# HBridge_Design.net
KiCad netlist of a schematic drawn in Altium Designer
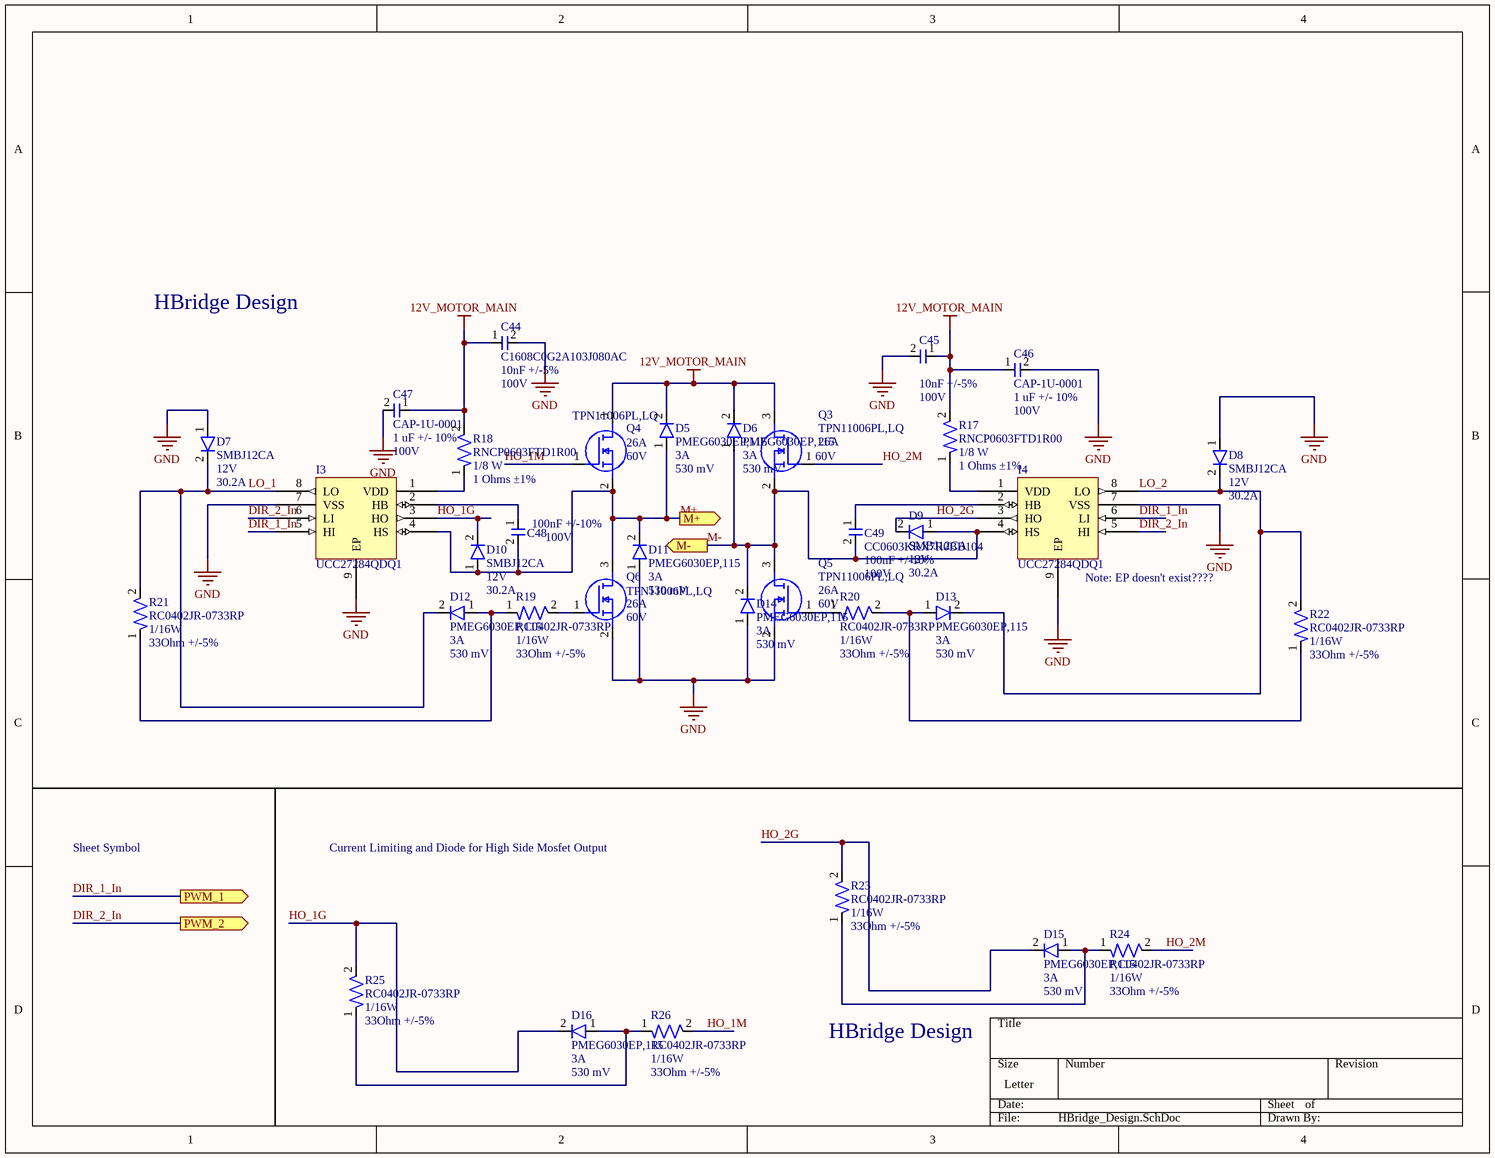
[diagram p0: HBridge_Design.SchDoc]

(export (version "E")
  (design (tool "Eeschema 10.0.6"))
  (components
    (comp (ref "C44")
      (value "C1608C0G2A103J080AC")
      (footprint "CAP-0603")
      (description "CAP CER 10000PF 100V C0G 0603")
      (fields
        (field (name "MANUFACTURER") "TDK Corporation")
        (field (name "CAPACITANCE") "10nF +/-5%")
        (field (name "VOLTAGE RATING") "100V")
      )
      (libsource (lib "MasterLib") (part "CAP-10N-0002"))
    )
    (comp (ref "C45")
      (value "C1608C0G2A103J080AC")
      (footprint "CAP-0603")
      (description "CAP CER 10000PF 100V C0G 0603")
      (fields
        (field (name "MANUFACTURER") "TDK Corporation")
        (field (name "CAPACITANCE") "10nF +/-5%")
        (field (name "VOLTAGE RATING") "100V")
      )
      (libsource (lib "MasterLib") (part "CAP-10N-0002"))
    )
    (comp (ref "C46")
      (value "CAP-1U-0001")
      (footprint "CAP-1206 - duplicate")
      (description "1 µF ±10% 100V Ceramic Capacitor X7R 1206 (3216 Metric)")
      (fields (field (name "CAPACITANCE") "1 uF +/- 10%") (field (name "VOLTAGE") "100V"))
      (libsource (lib "MasterLib") (part "CAP-1U-0001"))
    )
    (comp (ref "C47")
      (value "CAP-1U-0001")
      (footprint "CAP-1206 - duplicate")
      (description "1 µF ±10% 100V Ceramic Capacitor X7R 1206 (3216 Metric)")
      (fields (field (name "CAPACITANCE") "1 uF +/- 10%") (field (name "VOLTAGE") "100V"))
      (libsource (lib "MasterLib") (part "CAP-1U-0001"))
    )
    (comp (ref "C48")
      (value "CC0603KRX7R0BB104")
      (footprint "CAP-0603")
      (description "CAP CER 0.1UF 100V X7R 0603")
      (fields
        (field (name "MANUFACTURER") "YAGEO")
        (field (name "CAPACITANCE") "100nF +/-10%")
        (field (name "VOLTAGE RATING") "100V")
      )
      (libsource (lib "MasterLib") (part "CAP-100N-0001"))
    )
    (comp (ref "C49")
      (value "CC0603KRX7R0BB104")
      (footprint "CAP-0603")
      (description "CAP CER 0.1UF 100V X7R 0603")
      (fields
        (field (name "MANUFACTURER") "YAGEO")
        (field (name "CAPACITANCE") "100nF +/-10%")
        (field (name "VOLTAGE RATING") "100V")
      )
      (libsource (lib "MasterLib") (part "CAP-100N-0001"))
    )
    (comp (ref "D5")
      (value "PMEG6030EP,115")
      (footprint "DIO-SOD128")
      (description "Diode Schottky 60 V 3A Surface Mount SOD-128/CFP5")
      (fields
        (field (name "MANUFACTURER") "Nexperia USA Inc.")
        (field (name "CURRENT RATING") "3A")
        (field (name "VF (VOLTAGE FORWARD)") "530 mV")
      )
      (libsource (lib "MasterLib") (part "DIO-0.53V-0001"))
    )
    (comp (ref "D6")
      (value "PMEG6030EP,115")
      (footprint "DIO-SOD128")
      (description "Diode Schottky 60 V 3A Surface Mount SOD-128/CFP5")
      (fields
        (field (name "MANUFACTURER") "Nexperia USA Inc.")
        (field (name "CURRENT RATING") "3A")
        (field (name "VF (VOLTAGE FORWARD)") "530 mV")
      )
      (libsource (lib "MasterLib") (part "DIO-0.53V-0001"))
    )
    (comp (ref "D7")
      (value "SMBJ12CA")
      (footprint "DO-214AA (SMBJ)")
      (description "19.9V Clamp 30.2A Ipp Tvs Diode Surface Mount DO-214AA (SMBJ)")
      (fields
        (field (name "MANUFACTURER") "Littlefuse Inc.")
        (field (name "STANDOFF VOLTAGE") "12V")
        (field (name "CURRENT RATING") "30.2A")
      )
      (libsource (lib "MasterLib") (part "DIO-19.9V-0001"))
    )
    (comp (ref "D8")
      (value "SMBJ12CA")
      (footprint "DO-214AA (SMBJ)")
      (description "19.9V Clamp 30.2A Ipp Tvs Diode Surface Mount DO-214AA (SMBJ)")
      (fields
        (field (name "MANUFACTURER") "Littlefuse Inc.")
        (field (name "STANDOFF VOLTAGE") "12V")
        (field (name "CURRENT RATING") "30.2A")
      )
      (libsource (lib "MasterLib") (part "DIO-19.9V-0001"))
    )
    (comp (ref "D9")
      (value "SMBJ12CA")
      (footprint "DO-214AA (SMBJ)")
      (description "19.9V Clamp 30.2A Ipp Tvs Diode Surface Mount DO-214AA (SMBJ)")
      (fields
        (field (name "MANUFACTURER") "Littlefuse Inc.")
        (field (name "STANDOFF VOLTAGE") "12V")
        (field (name "CURRENT RATING") "30.2A")
      )
      (libsource (lib "MasterLib") (part "DIO-19.9V-0001"))
    )
    (comp (ref "D10")
      (value "SMBJ12CA")
      (footprint "DO-214AA (SMBJ)")
      (description "19.9V Clamp 30.2A Ipp Tvs Diode Surface Mount DO-214AA (SMBJ)")
      (fields
        (field (name "MANUFACTURER") "Littlefuse Inc.")
        (field (name "STANDOFF VOLTAGE") "12V")
        (field (name "CURRENT RATING") "30.2A")
      )
      (libsource (lib "MasterLib") (part "DIO-19.9V-0001"))
    )
    (comp (ref "D11")
      (value "PMEG6030EP,115")
      (footprint "DIO-SOD128")
      (description "Diode Schottky 60 V 3A Surface Mount SOD-128/CFP5")
      (fields
        (field (name "MANUFACTURER") "Nexperia USA Inc.")
        (field (name "CURRENT RATING") "3A")
        (field (name "VF (VOLTAGE FORWARD)") "530 mV")
      )
      (libsource (lib "MasterLib") (part "DIO-0.53V-0001"))
    )
    (comp (ref "D12")
      (value "PMEG6030EP,115")
      (footprint "DIO-SOD128")
      (description "Diode Schottky 60 V 3A Surface Mount SOD-128/CFP5")
      (fields
        (field (name "MANUFACTURER") "Nexperia USA Inc.")
        (field (name "CURRENT RATING") "3A")
        (field (name "VF (VOLTAGE FORWARD)") "530 mV")
      )
      (libsource (lib "MasterLib") (part "DIO-0.53V-0001"))
    )
    (comp (ref "D13")
      (value "PMEG6030EP,115")
      (footprint "DIO-SOD128")
      (description "Diode Schottky 60 V 3A Surface Mount SOD-128/CFP5")
      (fields
        (field (name "MANUFACTURER") "Nexperia USA Inc.")
        (field (name "CURRENT RATING") "3A")
        (field (name "VF (VOLTAGE FORWARD)") "530 mV")
      )
      (libsource (lib "MasterLib") (part "DIO-0.53V-0001"))
    )
    (comp (ref "D14")
      (value "PMEG6030EP,115")
      (footprint "DIO-SOD128")
      (description "Diode Schottky 60 V 3A Surface Mount SOD-128/CFP5")
      (fields
        (field (name "MANUFACTURER") "Nexperia USA Inc.")
        (field (name "CURRENT RATING") "3A")
        (field (name "VF (VOLTAGE FORWARD)") "530 mV")
      )
      (libsource (lib "MasterLib") (part "DIO-0.53V-0001"))
    )
    (comp (ref "D15")
      (value "PMEG6030EP,115")
      (footprint "DIO-SOD128")
      (description "Diode Schottky 60 V 3A Surface Mount SOD-128/CFP5")
      (fields
        (field (name "MANUFACTURER") "Nexperia USA Inc.")
        (field (name "CURRENT RATING") "3A")
        (field (name "VF (VOLTAGE FORWARD)") "530 mV")
      )
      (libsource (lib "MasterLib") (part "DIO-0.53V-0001"))
    )
    (comp (ref "D16")
      (value "PMEG6030EP,115")
      (footprint "DIO-SOD128")
      (description "Diode Schottky 60 V 3A Surface Mount SOD-128/CFP5")
      (fields
        (field (name "MANUFACTURER") "Nexperia USA Inc.")
        (field (name "CURRENT RATING") "3A")
        (field (name "VF (VOLTAGE FORWARD)") "530 mV")
      )
      (libsource (lib "MasterLib") (part "DIO-0.53V-0001"))
    )
    (comp (ref "I3")
      (value "UCC27284QDQ1")
      (footprint "IC-BUCK-8SOIC")
      (fields (field (name "MANUFACTURER") "Texas Instruments"))
      (libsource (lib "") (part "IC-GDRV-0001_1"))
    )
    (comp (ref "I4")
      (value "UCC27284QDQ1")
      (footprint "IC-BUCK-8SOIC")
      (fields (field (name "MANUFACTURER") "Texas Instruments"))
      (libsource (lib "MasterLib") (part "IC-GDRV-0001"))
    )
    (comp (ref "Q3")
      (value "TPN11006PL,LQ")
      (footprint "NMOS-8TSON")
      (description "MOSFET N-CH 60V 200MA SOT23")
      (fields
        (field (name "MANUFACTURER") "Toshiba")
        (field (name "ID-CONTINUOUS") "26A")
        (field (name "VDS-MAX") "60V")
      )
      (libsource (lib "MasterLib") (part "NMOS-26A-0001"))
    )
    (comp (ref "Q4")
      (value "TPN11006PL,LQ")
      (footprint "NMOS-8TSON")
      (description "MOSFET N-CH 60V 200MA SOT23")
      (fields
        (field (name "MANUFACTURER") "Toshiba")
        (field (name "ID-CONTINUOUS") "26A")
        (field (name "VDS-MAX") "60V")
      )
      (libsource (lib "MasterLib") (part "NMOS-26A-0001"))
    )
    (comp (ref "Q5")
      (value "TPN11006PL,LQ")
      (footprint "NMOS-8TSON")
      (description "MOSFET N-CH 60V 200MA SOT23")
      (fields
        (field (name "MANUFACTURER") "Toshiba")
        (field (name "ID-CONTINUOUS") "26A")
        (field (name "VDS-MAX") "60V")
      )
      (libsource (lib "MasterLib") (part "NMOS-26A-0001"))
    )
    (comp (ref "Q6")
      (value "TPN11006PL,LQ")
      (footprint "NMOS-8TSON")
      (description "MOSFET N-CH 60V 200MA SOT23")
      (fields
        (field (name "MANUFACTURER") "Toshiba")
        (field (name "ID-CONTINUOUS") "26A")
        (field (name "VDS-MAX") "60V")
      )
      (libsource (lib "MasterLib") (part "NMOS-26A-0001"))
    )
    (comp (ref "R17")
      (value "RNCP0603FTD1R00")
      (footprint "RES-0603")
      (description "1 Ohms ±1% 0.125W, 1/8W Chip Resistor 0603 (1608 Metric) Anti-Sulfur Thin Film")
      (fields (field (name "POWER") "1/8 W") (field (name "RESISTANCE") "1 Ohms ±1%"))
      (libsource (lib "MasterLib") (part "RES-1-0001"))
    )
    (comp (ref "R18")
      (value "RNCP0603FTD1R00")
      (footprint "RES-0603")
      (description "1 Ohms ±1% 0.125W, 1/8W Chip Resistor 0603 (1608 Metric) Anti-Sulfur Thin Film")
      (fields (field (name "POWER") "1/8 W") (field (name "RESISTANCE") "1 Ohms ±1%"))
      (libsource (lib "MasterLib") (part "RES-1-0001"))
    )
    (comp (ref "R19")
      (value "RC0402JR-0733RP")
      (footprint "RES-0402")
      (description "RES SMD 33 OHM 5% 1/16W 0402")
      (fields
        (field (name "MANUFACTURER") "YAGEO")
        (field (name "POWER RATING") "1/16W")
        (field (name "RESISTANCE") "33Ohm +/-5%")
      )
      (libsource (lib "MasterLib") (part "RES-33-0001"))
    )
    (comp (ref "R20")
      (value "RC0402JR-0733RP")
      (footprint "RES-0402")
      (description "RES SMD 33 OHM 5% 1/16W 0402")
      (fields
        (field (name "MANUFACTURER") "YAGEO")
        (field (name "POWER RATING") "1/16W")
        (field (name "RESISTANCE") "33Ohm +/-5%")
      )
      (libsource (lib "MasterLib") (part "RES-33-0001"))
    )
    (comp (ref "R21")
      (value "RC0402JR-0733RP")
      (footprint "RES-0402")
      (description "RES SMD 33 OHM 5% 1/16W 0402")
      (fields
        (field (name "MANUFACTURER") "YAGEO")
        (field (name "POWER RATING") "1/16W")
        (field (name "RESISTANCE") "33Ohm +/-5%")
      )
      (libsource (lib "MasterLib") (part "RES-33-0001"))
    )
    (comp (ref "R22")
      (value "RC0402JR-0733RP")
      (footprint "RES-0402")
      (description "RES SMD 33 OHM 5% 1/16W 0402")
      (fields
        (field (name "MANUFACTURER") "YAGEO")
        (field (name "POWER RATING") "1/16W")
        (field (name "RESISTANCE") "33Ohm +/-5%")
      )
      (libsource (lib "MasterLib") (part "RES-33-0001"))
    )
    (comp (ref "R23")
      (value "RC0402JR-0733RP")
      (footprint "RES-0402")
      (description "RES SMD 33 OHM 5% 1/16W 0402")
      (fields
        (field (name "MANUFACTURER") "YAGEO")
        (field (name "POWER RATING") "1/16W")
        (field (name "RESISTANCE") "33Ohm +/-5%")
      )
      (libsource (lib "MasterLib") (part "RES-33-0001"))
    )
    (comp (ref "R24")
      (value "RC0402JR-0733RP")
      (footprint "RES-0402")
      (description "RES SMD 33 OHM 5% 1/16W 0402")
      (fields
        (field (name "MANUFACTURER") "YAGEO")
        (field (name "POWER RATING") "1/16W")
        (field (name "RESISTANCE") "33Ohm +/-5%")
      )
      (libsource (lib "MasterLib") (part "RES-33-0001"))
    )
    (comp (ref "R25")
      (value "RC0402JR-0733RP")
      (footprint "RES-0402")
      (description "RES SMD 33 OHM 5% 1/16W 0402")
      (fields
        (field (name "MANUFACTURER") "YAGEO")
        (field (name "POWER RATING") "1/16W")
        (field (name "RESISTANCE") "33Ohm +/-5%")
      )
      (libsource (lib "MasterLib") (part "RES-33-0001"))
    )
    (comp (ref "R26")
      (value "RC0402JR-0733RP")
      (footprint "RES-0402")
      (description "RES SMD 33 OHM 5% 1/16W 0402")
      (fields
        (field (name "MANUFACTURER") "YAGEO")
        (field (name "POWER RATING") "1/16W")
        (field (name "RESISTANCE") "33Ohm +/-5%")
      )
      (libsource (lib "MasterLib") (part "RES-33-0001"))
    )
  )
  (nets
    (net (code "1") (name "/DIR_1_In") (class "Default")
      (node (ref "I3") (pin "5") (pinfunction "HI_5") (pintype "input"))
      (node (ref "I4") (pin "6") (pinfunction "LI_6") (pintype "input"))
    )
    (net (code "2") (name "/DIR_2_In") (class "Default")
      (node (ref "I3") (pin "6") (pinfunction "LI_6") (pintype "input"))
      (node (ref "I4") (pin "5") (pinfunction "HI_5") (pintype "input"))
    )
    (net (code "3") (name "/HO_1G") (class "Default")
      (node (ref "D10") (pin "2") (pintype "passive"))
      (node (ref "D16") (pin "2") (pintype "passive"))
      (node (ref "I3") (pin "3") (pinfunction "HO_3") (pintype "output"))
      (node (ref "R25") (pin "2") (pinfunction "2_2") (pintype "passive"))
    )
    (net (code "4") (name "/HO_1M") (class "Default")
      (node (ref "Q4") (pin "1") (pinfunction "G_1") (pintype "passive"))
      (node (ref "R26") (pin "2") (pinfunction "2_2") (pintype "passive"))
    )
    (net (code "5") (name "/HO_2G") (class "Default")
      (node (ref "D15") (pin "2") (pintype "passive"))
      (node (ref "D9") (pin "2") (pintype "passive"))
      (node (ref "I4") (pin "3") (pinfunction "HO_3") (pintype "output"))
      (node (ref "R23") (pin "2") (pinfunction "2_2") (pintype "passive"))
    )
    (net (code "6") (name "/HO_2M") (class "Default")
      (node (ref "Q3") (pin "1") (pinfunction "G_1") (pintype "passive"))
      (node (ref "R24") (pin "2") (pinfunction "2_2") (pintype "passive"))
    )
    (net (code "7") (name "/LO_1") (class "Default")
      (node (ref "D12") (pin "2") (pintype "passive"))
      (node (ref "D7") (pin "2") (pintype "passive"))
      (node (ref "I3") (pin "8") (pinfunction "LO_8") (pintype "output"))
      (node (ref "R21") (pin "2") (pinfunction "2_2") (pintype "passive"))
    )
    (net (code "8") (name "/LO_2") (class "Default")
      (node (ref "D13") (pin "2") (pintype "passive"))
      (node (ref "D8") (pin "2") (pintype "passive"))
      (node (ref "I4") (pin "8") (pinfunction "LO_8") (pintype "output"))
      (node (ref "R22") (pin "2") (pinfunction "2_2") (pintype "passive"))
    )
    (net (code "9") (name "/M+") (class "Default")
      (node (ref "C48") (pin "2") (pinfunction "2_2") (pintype "passive"))
      (node (ref "D10") (pin "1") (pintype "passive"))
      (node (ref "D11") (pin "2") (pintype "passive"))
      (node (ref "D5") (pin "1") (pintype "passive"))
      (node (ref "I3") (pin "4") (pinfunction "HS_4") (pintype "bidirectional"))
      (node (ref "Q4") (pin "2") (pinfunction "S_2") (pintype "passive"))
      (node (ref "Q6") (pin "3") (pinfunction "D_3") (pintype "passive"))
    )
    (net (code "10") (name "/M-") (class "Default")
      (node (ref "C49") (pin "2") (pinfunction "2_2") (pintype "passive"))
      (node (ref "D14") (pin "2") (pintype "passive"))
      (node (ref "D6") (pin "1") (pintype "passive"))
      (node (ref "D9") (pin "1") (pintype "passive"))
      (node (ref "I4") (pin "4") (pinfunction "HS_4") (pintype "bidirectional"))
      (node (ref "Q3") (pin "2") (pinfunction "S_2") (pintype "passive"))
      (node (ref "Q5") (pin "3") (pinfunction "D_3") (pintype "passive"))
    )
    (net (code "11") (name "12V_MOTOR_MAIN") (class "Default")
      (node (ref "C44") (pin "1") (pinfunction "1_1") (pintype "passive"))
      (node (ref "C45") (pin "1") (pinfunction "1_1") (pintype "passive"))
      (node (ref "C46") (pin "1") (pinfunction "1_1") (pintype "passive"))
      (node (ref "C47") (pin "1") (pinfunction "1_1") (pintype "passive"))
      (node (ref "D5") (pin "2") (pintype "passive"))
      (node (ref "D6") (pin "2") (pintype "passive"))
      (node (ref "Q3") (pin "3") (pinfunction "D_3") (pintype "passive"))
      (node (ref "Q4") (pin "3") (pinfunction "D_3") (pintype "passive"))
      (node (ref "R17") (pin "2") (pinfunction "2_2") (pintype "passive"))
      (node (ref "R18") (pin "2") (pinfunction "2_2") (pintype "passive"))
    )
    (net (code "12") (name "GND") (class "Default")
      (node (ref "C44") (pin "2") (pinfunction "2_2") (pintype "passive"))
      (node (ref "C45") (pin "2") (pinfunction "2_2") (pintype "passive"))
      (node (ref "C46") (pin "2") (pinfunction "2_2") (pintype "passive"))
      (node (ref "C47") (pin "2") (pinfunction "2_2") (pintype "passive"))
      (node (ref "D11") (pin "1") (pintype "passive"))
      (node (ref "D14") (pin "1") (pintype "passive"))
      (node (ref "D7") (pin "1") (pintype "passive"))
      (node (ref "D8") (pin "1") (pintype "passive"))
      (node (ref "I3") (pin "7") (pinfunction "VSS_7") (pintype "power_in"))
      (node (ref "I3") (pin "9") (pinfunction "EP_9") (pintype "power_in"))
      (node (ref "I4") (pin "7") (pinfunction "VSS_7") (pintype "power_in"))
      (node (ref "I4") (pin "9") (pinfunction "EP_9") (pintype "power_in"))
      (node (ref "Q5") (pin "2") (pinfunction "S_2") (pintype "passive"))
      (node (ref "Q6") (pin "2") (pinfunction "S_2") (pintype "passive"))
    )
    (net (code "13") (name "Net-(D12-Pad1)") (class "Default")
      (node (ref "D12") (pin "1") (pintype "passive"))
      (node (ref "R19") (pin "1") (pinfunction "1_1") (pintype "passive"))
      (node (ref "R21") (pin "1") (pinfunction "1_1") (pintype "passive"))
    )
    (net (code "14") (name "Net-(D13-Pad1)") (class "Default")
      (node (ref "D13") (pin "1") (pintype "passive"))
      (node (ref "R20") (pin "2") (pinfunction "2_2") (pintype "passive"))
      (node (ref "R22") (pin "1") (pinfunction "1_1") (pintype "passive"))
    )
    (net (code "15") (name "Net-(D15-Pad1)") (class "Default")
      (node (ref "D15") (pin "1") (pintype "passive"))
      (node (ref "R23") (pin "1") (pinfunction "1_1") (pintype "passive"))
      (node (ref "R24") (pin "1") (pinfunction "1_1") (pintype "passive"))
    )
    (net (code "16") (name "Net-(D16-Pad1)") (class "Default")
      (node (ref "D16") (pin "1") (pintype "passive"))
      (node (ref "R25") (pin "1") (pinfunction "1_1") (pintype "passive"))
      (node (ref "R26") (pin "1") (pinfunction "1_1") (pintype "passive"))
    )
    (net (code "17") (name "Net-(I3-HB)") (class "Default")
      (node (ref "C48") (pin "1") (pinfunction "1_1") (pintype "passive"))
      (node (ref "I3") (pin "2") (pinfunction "HB_2") (pintype "bidirectional"))
    )
    (net (code "18") (name "Net-(I3-VDD)") (class "Default")
      (node (ref "I3") (pin "1") (pinfunction "VDD_1") (pintype "power_in"))
      (node (ref "R18") (pin "1") (pinfunction "1_1") (pintype "passive"))
    )
    (net (code "19") (name "Net-(I4-HB)") (class "Default")
      (node (ref "C49") (pin "1") (pinfunction "1_1") (pintype "passive"))
      (node (ref "I4") (pin "2") (pinfunction "HB_2") (pintype "bidirectional"))
    )
    (net (code "20") (name "Net-(I4-VDD)") (class "Default")
      (node (ref "I4") (pin "1") (pinfunction "VDD_1") (pintype "power_in"))
      (node (ref "R17") (pin "1") (pinfunction "1_1") (pintype "passive"))
    )
    (net (code "21") (name "Net-(Q5-G)") (class "Default")
      (node (ref "Q5") (pin "1") (pinfunction "G_1") (pintype "passive"))
      (node (ref "R20") (pin "1") (pinfunction "1_1") (pintype "passive"))
    )
    (net (code "22") (name "Net-(Q6-G)") (class "Default")
      (node (ref "Q6") (pin "1") (pinfunction "G_1") (pintype "passive"))
      (node (ref "R19") (pin "2") (pinfunction "2_2") (pintype "passive"))
    )
  )
)
